# Jar_of_Fireflies.net
KiCad netlist of a schematic drawn in EAGLE
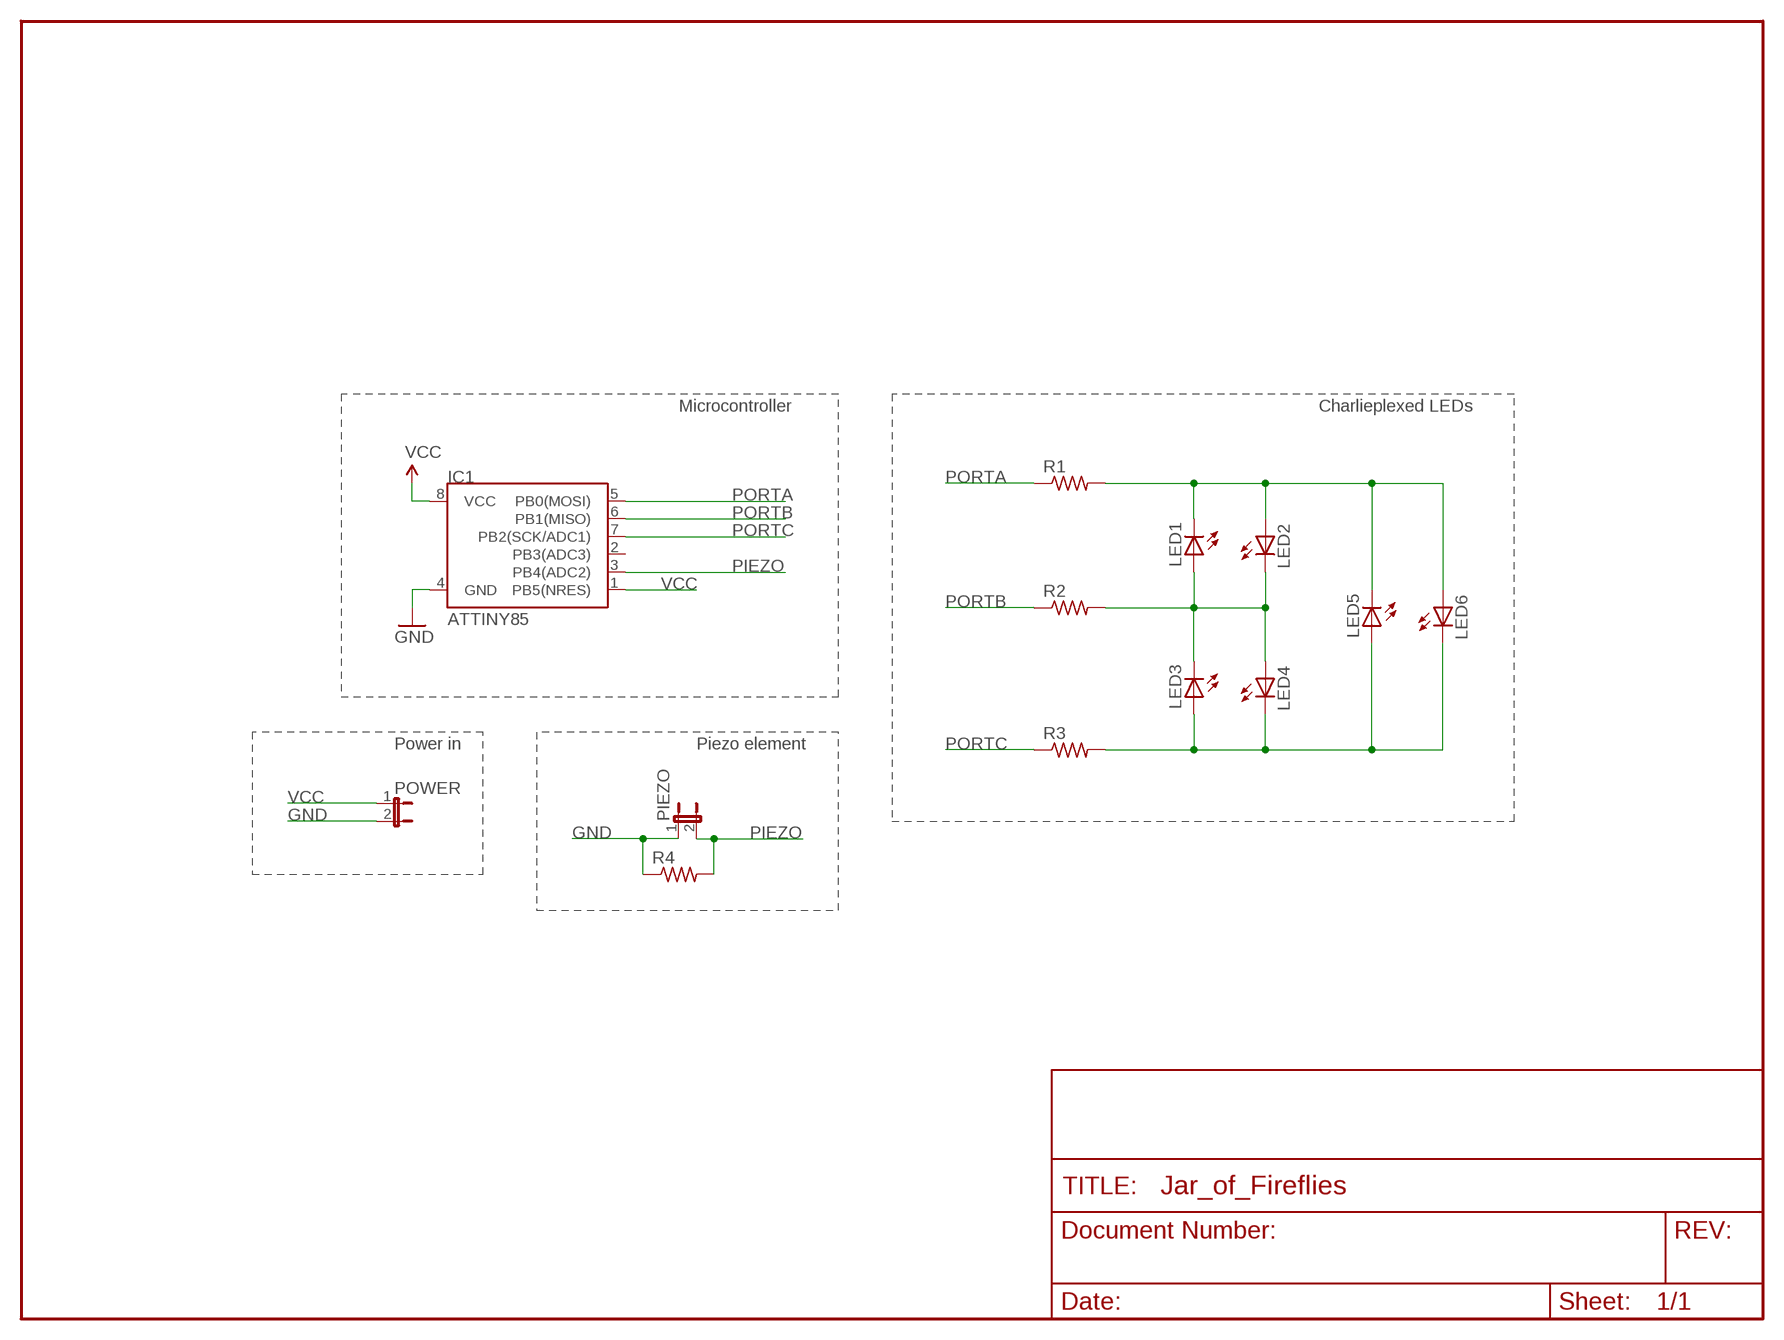
[diagram p0: schematic, sheet 1]

(export (version "E")
  (design (tool "Eeschema 10.0.6"))
  (components
    (comp (ref "IC1")
      (value "ATTINY85")
      (footprint "eagle-import:DIP08")
      (libsource (lib "eagle-import") (part "ATTINY45DIP8"))
    )
    (comp (ref "LED1")
      (value "LED5MM")
      (footprint "eagle-import:LED5MM")
      (libsource (lib "eagle-import") (part "LED5MM"))
    )
    (comp (ref "LED2")
      (value "LED5MM")
      (footprint "eagle-import:LED5MM")
      (libsource (lib "eagle-import") (part "LED5MM"))
    )
    (comp (ref "LED3")
      (value "LED5MM")
      (footprint "eagle-import:LED5MM")
      (libsource (lib "eagle-import") (part "LED5MM"))
    )
    (comp (ref "LED4")
      (value "LED5MM")
      (footprint "eagle-import:LED5MM")
      (libsource (lib "eagle-import") (part "LED5MM"))
    )
    (comp (ref "LED5")
      (value "LED5MM")
      (footprint "eagle-import:LED5MM")
      (libsource (lib "eagle-import") (part "LED5MM"))
    )
    (comp (ref "LED6")
      (value "LED5MM")
      (footprint "eagle-import:LED5MM")
      (libsource (lib "eagle-import") (part "LED5MM"))
    )
    (comp (ref "PIEZO")
      (value "JUMPER-2PTH")
      (footprint "eagle-import:1X02")
      (libsource (lib "eagle-import") (part "JUMPER-2PTH"))
    )
    (comp (ref "POWER")
      (value "JUMPER-2PTH")
      (footprint "eagle-import:1X02")
      (libsource (lib "eagle-import") (part "JUMPER-2PTH"))
    )
    (comp (ref "R1")
      (value "R-US_0207/2V")
      (footprint "eagle-import:0207_2V")
      (libsource (lib "eagle-import") (part "R-US_0207/2V"))
    )
    (comp (ref "R2")
      (value "R-US_0204/7")
      (footprint "eagle-import:0204_7")
      (libsource (lib "eagle-import") (part "R-US_0204/7"))
    )
    (comp (ref "R3")
      (value "R-US_0207/2V")
      (footprint "eagle-import:0207_2V")
      (libsource (lib "eagle-import") (part "R-US_0207/2V"))
    )
    (comp (ref "R4")
      (value "R-US_0204/7")
      (footprint "eagle-import:0204_7")
      (libsource (lib "eagle-import") (part "R-US_0204/7"))
    )
  )
  (nets
    (net (code "1") (name "/PIEZO") (class "Default")
      (node (ref "IC1") (pin "3") (pinfunction "PB4(ADC2)_3") (pintype "bidirectional"))
      (node (ref "PIEZO") (pin "2") (pinfunction "2_2") (pintype "passive"))
      (node (ref "R4") (pin "2") (pinfunction "2_2") (pintype "passive"))
    )
    (net (code "2") (name "/PORTA") (class "Default")
      (node (ref "IC1") (pin "5") (pinfunction "PB0(MOSI)_5") (pintype "bidirectional"))
      (node (ref "R1") (pin "1") (pinfunction "1_1") (pintype "passive"))
    )
    (net (code "3") (name "/PORTB") (class "Default")
      (node (ref "IC1") (pin "6") (pinfunction "PB1(MISO)_6") (pintype "bidirectional"))
      (node (ref "R2") (pin "1") (pinfunction "1_1") (pintype "passive"))
    )
    (net (code "4") (name "/PORTC") (class "Default")
      (node (ref "IC1") (pin "7") (pinfunction "PB2(SCK/ADC1)_7") (pintype "bidirectional"))
      (node (ref "R3") (pin "1") (pinfunction "1_1") (pintype "passive"))
    )
    (net (code "5") (name "GND") (class "Default")
      (node (ref "IC1") (pin "4") (pinfunction "GND_4") (pintype "bidirectional"))
      (node (ref "PIEZO") (pin "1") (pinfunction "1_1") (pintype "passive"))
      (node (ref "POWER") (pin "2") (pinfunction "2_2") (pintype "passive"))
      (node (ref "R4") (pin "1") (pinfunction "1_1") (pintype "passive"))
    )
    (net (code "6") (name "Net-(LED1-C)") (class "Default")
      (node (ref "LED1") (pin "K") (pinfunction "C_K") (pintype "passive"))
      (node (ref "LED2") (pin "A") (pinfunction "A_A") (pintype "passive"))
      (node (ref "LED5") (pin "K") (pinfunction "C_K") (pintype "passive"))
      (node (ref "LED6") (pin "A") (pinfunction "A_A") (pintype "passive"))
      (node (ref "R1") (pin "2") (pinfunction "2_2") (pintype "passive"))
    )
    (net (code "7") (name "Net-(LED2-C)") (class "Default")
      (node (ref "LED1") (pin "A") (pinfunction "A_A") (pintype "passive"))
      (node (ref "LED2") (pin "K") (pinfunction "C_K") (pintype "passive"))
      (node (ref "LED3") (pin "K") (pinfunction "C_K") (pintype "passive"))
      (node (ref "LED4") (pin "A") (pinfunction "A_A") (pintype "passive"))
      (node (ref "R2") (pin "2") (pinfunction "2_2") (pintype "passive"))
    )
    (net (code "8") (name "Net-(LED4-C)") (class "Default")
      (node (ref "LED3") (pin "A") (pinfunction "A_A") (pintype "passive"))
      (node (ref "LED4") (pin "K") (pinfunction "C_K") (pintype "passive"))
      (node (ref "LED5") (pin "A") (pinfunction "A_A") (pintype "passive"))
      (node (ref "LED6") (pin "K") (pinfunction "C_K") (pintype "passive"))
      (node (ref "R3") (pin "2") (pinfunction "2_2") (pintype "passive"))
    )
    (net (code "9") (name "VCC") (class "Default")
      (node (ref "IC1") (pin "1") (pinfunction "PB5(NRES)_1") (pintype "bidirectional"))
      (node (ref "IC1") (pin "8") (pinfunction "VCC_8") (pintype "bidirectional"))
      (node (ref "POWER") (pin "1") (pinfunction "1_1") (pintype "passive"))
    )
    (net (code "10") (name "unconnected-(IC1-PB3(ADC3)-Pad2)") (class "Default")
      (node (ref "IC1") (pin "2") (pinfunction "PB3(ADC3)_2") (pintype "bidirectional"))
    )
  )
)
